# adcmp572-pulser.net
KiCad netlist of a schematic drawn in EAGLE
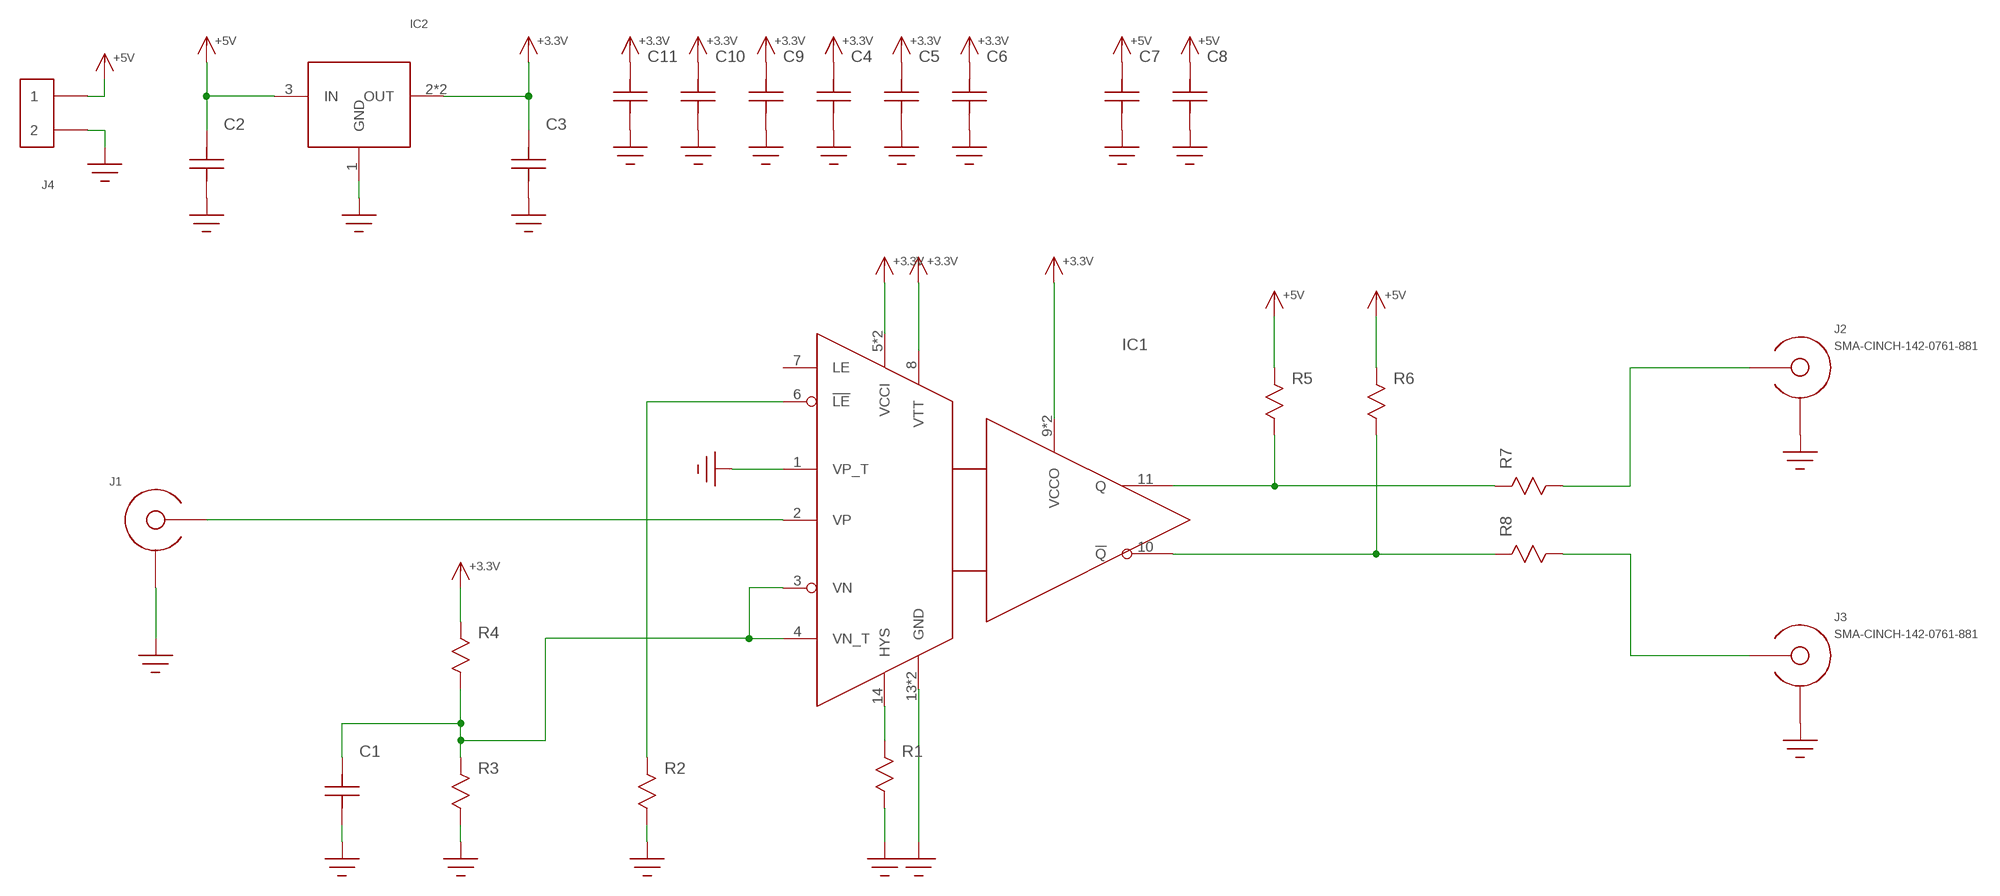
[diagram p0: schematic, sheet 1]

(export (version "E")
  (design (tool "Eeschema 10.0.6"))
  (components
    (comp (ref "C1")
      (value "C0603")
      (footprint "eagle-import:C0603")
      (libsource (lib "eagle-import") (part "C0603"))
    )
    (comp (ref "C2")
      (value "C1206")
      (footprint "eagle-import:1206")
      (libsource (lib "eagle-import") (part "C1206"))
    )
    (comp (ref "C3")
      (value "C1206")
      (footprint "eagle-import:1206")
      (libsource (lib "eagle-import") (part "C1206"))
    )
    (comp (ref "C4") (value "C") (footprint "eagle-import:C0402") (libsource (lib "eagle-import") (part "C")))
    (comp (ref "C5") (value "C") (footprint "eagle-import:C0402") (libsource (lib "eagle-import") (part "C")))
    (comp (ref "C6") (value "C") (footprint "eagle-import:C0402") (libsource (lib "eagle-import") (part "C")))
    (comp (ref "C7") (value "C") (footprint "eagle-import:C0402") (libsource (lib "eagle-import") (part "C")))
    (comp (ref "C8") (value "C") (footprint "eagle-import:C0402") (libsource (lib "eagle-import") (part "C")))
    (comp (ref "C9") (value "C") (footprint "eagle-import:C0402") (libsource (lib "eagle-import") (part "C")))
    (comp (ref "C10")
      (value "C0201")
      (footprint "eagle-import:0201")
      (libsource (lib "eagle-import") (part "C0201"))
    )
    (comp (ref "C11")
      (value "C0201")
      (footprint "eagle-import:0201")
      (libsource (lib "eagle-import") (part "C0201"))
    )
    (comp (ref "IC1")
      (value "ADCMP572")
      (footprint "eagle-import:TQFN16-EP")
      (libsource (lib "eagle-import") (part "ADCMP572"))
    )
    (comp (ref "IC2")
      (value "AZ1117E")
      (footprint "eagle-import:SOT-223")
      (libsource (lib "eagle-import") (part "AZ1117E"))
    )
    (comp (ref "J1")
      (value "SMA-EDGE-LAUNCH4L-4020-TAPER-FIXED")
      (footprint "eagle-import:SMA_EDGE_LAUNCH_4L_4020_TAPER_FIXED")
      (libsource (lib "eagle-import") (part "SMA-EDGE-LAUNCH4L-4020-TAPER-FIXED"))
    )
    (comp (ref "J2")
      (value "SMA-CINCH-142-0761-881")
      (footprint "eagle-import:SMA-CINCH-142-0761-881")
      (libsource (lib "eagle-import") (part "SMA-CINCH-142-0761-881"))
    )
    (comp (ref "J3")
      (value "SMA-CINCH-142-0761-881")
      (footprint "eagle-import:SMA-CINCH-142-0761-881")
      (libsource (lib "eagle-import") (part "SMA-CINCH-142-0761-881"))
    )
    (comp (ref "J4")
      (value "HEADER_2PIN")
      (footprint "eagle-import:HEADER_2PIN")
      (libsource (lib "eagle-import") (part "HEADER_2PIN"))
    )
    (comp (ref "R1")
      (value "R0603")
      (footprint "eagle-import:R0603")
      (libsource (lib "eagle-import") (part "R0603"))
    )
    (comp (ref "R2")
      (value "R0603")
      (footprint "eagle-import:R0603")
      (libsource (lib "eagle-import") (part "R0603"))
    )
    (comp (ref "R3")
      (value "R0603")
      (footprint "eagle-import:R0603")
      (libsource (lib "eagle-import") (part "R0603"))
    )
    (comp (ref "R4")
      (value "R0603")
      (footprint "eagle-import:R0603")
      (libsource (lib "eagle-import") (part "R0603"))
    )
    (comp (ref "R5")
      (value "R0402")
      (footprint "eagle-import:0402")
      (libsource (lib "eagle-import") (part "R0402"))
    )
    (comp (ref "R6")
      (value "R0402")
      (footprint "eagle-import:0402")
      (libsource (lib "eagle-import") (part "R0402"))
    )
    (comp (ref "R7")
      (value "R0402")
      (footprint "eagle-import:0402")
      (libsource (lib "eagle-import") (part "R0402"))
    )
    (comp (ref "R8")
      (value "R0402")
      (footprint "eagle-import:0402")
      (libsource (lib "eagle-import") (part "R0402"))
    )
  )
  (nets
    (net (code "1") (name "+3.3V") (class "Default")
      (node (ref "C10") (pin "P$2") (pinfunction "P$2_P$2") (pintype "bidirectional"))
      (node (ref "C11") (pin "P$2") (pinfunction "P$2_P$2") (pintype "bidirectional"))
      (node (ref "C3") (pin "P$2") (pinfunction "P$2_P$2") (pintype "bidirectional"))
      (node (ref "C4") (pin "2") (pinfunction "P$2_2") (pintype "bidirectional"))
      (node (ref "C5") (pin "2") (pinfunction "P$2_2") (pintype "bidirectional"))
      (node (ref "C6") (pin "2") (pinfunction "P$2_2") (pintype "bidirectional"))
      (node (ref "C9") (pin "2") (pinfunction "P$2_2") (pintype "bidirectional"))
      (node (ref "IC1") (pin "12") (pinfunction "VCCO_12") (pintype "bidirectional"))
      (node (ref "IC1") (pin "16") (pinfunction "VCCI_16") (pintype "bidirectional"))
      (node (ref "IC1") (pin "5") (pinfunction "VCCI_5") (pintype "bidirectional"))
      (node (ref "IC1") (pin "8") (pinfunction "VTT_8") (pintype "bidirectional"))
      (node (ref "IC1") (pin "9") (pinfunction "VCCO_9") (pintype "bidirectional"))
      (node (ref "IC2") (pin "2") (pinfunction "OUT_2") (pintype "bidirectional"))
      (node (ref "IC2") (pin "4") (pinfunction "OUT_4") (pintype "bidirectional"))
      (node (ref "R4") (pin "P$1") (pinfunction "P$3_P$1") (pintype "bidirectional"))
    )
    (net (code "2") (name "+5V") (class "Default")
      (node (ref "C2") (pin "P$2") (pinfunction "P$2_P$2") (pintype "bidirectional"))
      (node (ref "C7") (pin "2") (pinfunction "P$2_2") (pintype "bidirectional"))
      (node (ref "C8") (pin "2") (pinfunction "P$2_2") (pintype "bidirectional"))
      (node (ref "IC2") (pin "3") (pinfunction "IN_3") (pintype "bidirectional"))
      (node (ref "J4") (pin "1") (pinfunction "1_1") (pintype "bidirectional"))
      (node (ref "R5") (pin "1") (pinfunction "P$3_1") (pintype "bidirectional"))
      (node (ref "R6") (pin "1") (pinfunction "P$3_1") (pintype "bidirectional"))
    )
    (net (code "3") (name "GND") (class "Default")
      (node (ref "C1") (pin "P$1") (pinfunction "P$1_P$1") (pintype "bidirectional"))
      (node (ref "C10") (pin "P$1") (pinfunction "P$1_P$1") (pintype "bidirectional"))
      (node (ref "C11") (pin "P$1") (pinfunction "P$1_P$1") (pintype "bidirectional"))
      (node (ref "C2") (pin "P$1") (pinfunction "P$1_P$1") (pintype "bidirectional"))
      (node (ref "C3") (pin "P$1") (pinfunction "P$1_P$1") (pintype "bidirectional"))
      (node (ref "C4") (pin "1") (pinfunction "P$1_1") (pintype "bidirectional"))
      (node (ref "C5") (pin "1") (pinfunction "P$1_1") (pintype "bidirectional"))
      (node (ref "C6") (pin "1") (pinfunction "P$1_1") (pintype "bidirectional"))
      (node (ref "C7") (pin "1") (pinfunction "P$1_1") (pintype "bidirectional"))
      (node (ref "C8") (pin "1") (pinfunction "P$1_1") (pintype "bidirectional"))
      (node (ref "C9") (pin "1") (pinfunction "P$1_1") (pintype "bidirectional"))
      (node (ref "IC1") (pin "1") (pinfunction "VP_T_1") (pintype "bidirectional"))
      (node (ref "IC1") (pin "13") (pinfunction "GND_13") (pintype "bidirectional"))
      (node (ref "IC1") (pin "15") (pinfunction "GND_15") (pintype "bidirectional"))
      (node (ref "IC2") (pin "1") (pinfunction "GND_1") (pintype "bidirectional"))
      (node (ref "J1") (pin "BOTTOM_GND") (pinfunction "SHIELD_BOTTOM_GND") (pintype "bidirectional"))
      (node (ref "J1") (pin "GND@1") (pinfunction "SHIELD_GND@1") (pintype "bidirectional"))
      (node (ref "J1") (pin "GND@14") (pinfunction "SHIELD_GND@14") (pintype "bidirectional"))
      (node (ref "J1") (pin "GND@15") (pinfunction "SHIELD_GND@15") (pintype "bidirectional"))
      (node (ref "J1") (pin "GND@16") (pinfunction "SHIELD_GND@16") (pintype "bidirectional"))
      (node (ref "J1") (pin "GND@17") (pinfunction "SHIELD_GND@17") (pintype "bidirectional"))
      (node (ref "J1") (pin "GND@2") (pinfunction "SHIELD_GND@2") (pintype "bidirectional"))
      (node (ref "J1") (pin "GND@3") (pinfunction "SHIELD_GND@3") (pintype "bidirectional"))
      (node (ref "J1") (pin "GND@4") (pinfunction "SHIELD_GND@4") (pintype "bidirectional"))
      (node (ref "J1") (pin "GND@5") (pinfunction "SHIELD_GND@5") (pintype "bidirectional"))
      (node (ref "J1") (pin "GND@6") (pinfunction "SHIELD_GND@6") (pintype "bidirectional"))
      (node (ref "J1") (pin "GND@7") (pinfunction "SHIELD_GND@7") (pintype "bidirectional"))
      (node (ref "J1") (pin "GND@8") (pinfunction "SHIELD_GND@8") (pintype "bidirectional"))
      (node (ref "J1") (pin "GND_PAD1") (pinfunction "SHIELD_GND_PAD1") (pintype "bidirectional"))
      (node (ref "J1") (pin "GND_PAD2") (pinfunction "SHIELD_GND_PAD2") (pintype "bidirectional"))
      (node (ref "J1") (pin "P$1") (pinfunction "SHIELD_P$1") (pintype "bidirectional"))
      (node (ref "J1") (pin "P$2") (pinfunction "SHIELD_P$2") (pintype "bidirectional"))
      (node (ref "J2") (pin "GND@1") (pinfunction "SHIELD_GND@1") (pintype "bidirectional"))
      (node (ref "J2") (pin "GND@2") (pinfunction "SHIELD_GND@2") (pintype "bidirectional"))
      (node (ref "J2") (pin "GND@3") (pinfunction "SHIELD_GND@3") (pintype "bidirectional"))
      (node (ref "J2") (pin "HOLE@1") (pinfunction "SHIELD_HOLE@1") (pintype "bidirectional"))
      (node (ref "J2") (pin "HOLE@2") (pinfunction "SHIELD_HOLE@2") (pintype "bidirectional"))
      (node (ref "J2") (pin "HOLE@3") (pinfunction "SHIELD_HOLE@3") (pintype "bidirectional"))
      (node (ref "J2") (pin "HOLE@4") (pinfunction "SHIELD_HOLE@4") (pintype "bidirectional"))
      (node (ref "J2") (pin "VIA@1") (pinfunction "SHIELD_VIA@1") (pintype "bidirectional"))
      (node (ref "J2") (pin "VIA@2") (pinfunction "SHIELD_VIA@2") (pintype "bidirectional"))
      (node (ref "J2") (pin "VIA@3") (pinfunction "SHIELD_VIA@3") (pintype "bidirectional"))
      (node (ref "J2") (pin "VIA@4") (pinfunction "SHIELD_VIA@4") (pintype "bidirectional"))
      (node (ref "J2") (pin "VIA@5") (pinfunction "SHIELD_VIA@5") (pintype "bidirectional"))
      (node (ref "J2") (pin "VIA@6") (pinfunction "SHIELD_VIA@6") (pintype "bidirectional"))
      (node (ref "J3") (pin "GND@1") (pinfunction "SHIELD_GND@1") (pintype "bidirectional"))
      (node (ref "J3") (pin "GND@2") (pinfunction "SHIELD_GND@2") (pintype "bidirectional"))
      (node (ref "J3") (pin "GND@3") (pinfunction "SHIELD_GND@3") (pintype "bidirectional"))
      (node (ref "J3") (pin "HOLE@1") (pinfunction "SHIELD_HOLE@1") (pintype "bidirectional"))
      (node (ref "J3") (pin "HOLE@2") (pinfunction "SHIELD_HOLE@2") (pintype "bidirectional"))
      (node (ref "J3") (pin "HOLE@3") (pinfunction "SHIELD_HOLE@3") (pintype "bidirectional"))
      (node (ref "J3") (pin "HOLE@4") (pinfunction "SHIELD_HOLE@4") (pintype "bidirectional"))
      (node (ref "J3") (pin "VIA@1") (pinfunction "SHIELD_VIA@1") (pintype "bidirectional"))
      (node (ref "J3") (pin "VIA@2") (pinfunction "SHIELD_VIA@2") (pintype "bidirectional"))
      (node (ref "J3") (pin "VIA@3") (pinfunction "SHIELD_VIA@3") (pintype "bidirectional"))
      (node (ref "J3") (pin "VIA@4") (pinfunction "SHIELD_VIA@4") (pintype "bidirectional"))
      (node (ref "J3") (pin "VIA@5") (pinfunction "SHIELD_VIA@5") (pintype "bidirectional"))
      (node (ref "J3") (pin "VIA@6") (pinfunction "SHIELD_VIA@6") (pintype "bidirectional"))
      (node (ref "J4") (pin "2") (pinfunction "2_2") (pintype "bidirectional"))
      (node (ref "R1") (pin "P$2") (pinfunction "P$4_P$2") (pintype "bidirectional"))
      (node (ref "R2") (pin "P$2") (pinfunction "P$4_P$2") (pintype "bidirectional"))
      (node (ref "R3") (pin "P$2") (pinfunction "P$4_P$2") (pintype "bidirectional"))
    )
    (net (code "4") (name "Net-(IC1-HYS)") (class "Default")
      (node (ref "IC1") (pin "14") (pinfunction "HYS_14") (pintype "bidirectional"))
      (node (ref "R1") (pin "P$1") (pinfunction "P$3_P$1") (pintype "bidirectional"))
    )
    (net (code "5") (name "Net-(IC1-Q)") (class "Default")
      (node (ref "IC1") (pin "11") (pinfunction "Q_11") (pintype "bidirectional"))
      (node (ref "R5") (pin "2") (pinfunction "P$4_2") (pintype "bidirectional"))
      (node (ref "R7") (pin "1") (pinfunction "P$3_1") (pintype "bidirectional"))
    )
    (net (code "6") (name "Net-(IC1-VN)") (class "Default")
      (node (ref "C1") (pin "P$2") (pinfunction "P$2_P$2") (pintype "bidirectional"))
      (node (ref "IC1") (pin "3") (pinfunction "VN_3") (pintype "bidirectional"))
      (node (ref "IC1") (pin "4") (pinfunction "VN_T_4") (pintype "bidirectional"))
      (node (ref "R3") (pin "P$1") (pinfunction "P$3_P$1") (pintype "bidirectional"))
      (node (ref "R4") (pin "P$2") (pinfunction "P$4_P$2") (pintype "bidirectional"))
    )
    (net (code "7") (name "Net-(IC1-VP)") (class "Default")
      (node (ref "IC1") (pin "2") (pinfunction "VP_2") (pintype "bidirectional"))
      (node (ref "J1") (pin "CENTER@1") (pinfunction "CENTER_CENTER@1") (pintype "bidirectional"))
      (node (ref "J1") (pin "P$3") (pinfunction "CENTER_P$3") (pintype "bidirectional"))
    )
    (net (code "8") (name "Net-(IC1-~{LE})") (class "Default")
      (node (ref "IC1") (pin "6") (pinfunction "~{LE}_6") (pintype "bidirectional"))
      (node (ref "R2") (pin "P$1") (pinfunction "P$3_P$1") (pintype "bidirectional"))
    )
    (net (code "9") (name "Net-(IC1-~{Q})") (class "Default")
      (node (ref "IC1") (pin "10") (pinfunction "~{Q}_10") (pintype "bidirectional"))
      (node (ref "R6") (pin "2") (pinfunction "P$4_2") (pintype "bidirectional"))
      (node (ref "R8") (pin "1") (pinfunction "P$3_1") (pintype "bidirectional"))
    )
    (net (code "10") (name "Net-(R7-P$4)") (class "Default")
      (node (ref "J2") (pin "CENTER") (pinfunction "CENTER_CENTER") (pintype "bidirectional"))
      (node (ref "R7") (pin "2") (pinfunction "P$4_2") (pintype "bidirectional"))
    )
    (net (code "11") (name "Net-(R8-P$4)") (class "Default")
      (node (ref "J3") (pin "CENTER") (pinfunction "CENTER_CENTER") (pintype "bidirectional"))
      (node (ref "R8") (pin "2") (pinfunction "P$4_2") (pintype "bidirectional"))
    )
    (net (code "12") (name "unconnected-(IC1-LE-Pad7)") (class "Default")
      (node (ref "IC1") (pin "7") (pinfunction "LE_7") (pintype "bidirectional"))
    )
  )
)
